# LTM8055_AddonBoard_v1_1.net
KiCad netlist of a schematic drawn in EAGLE
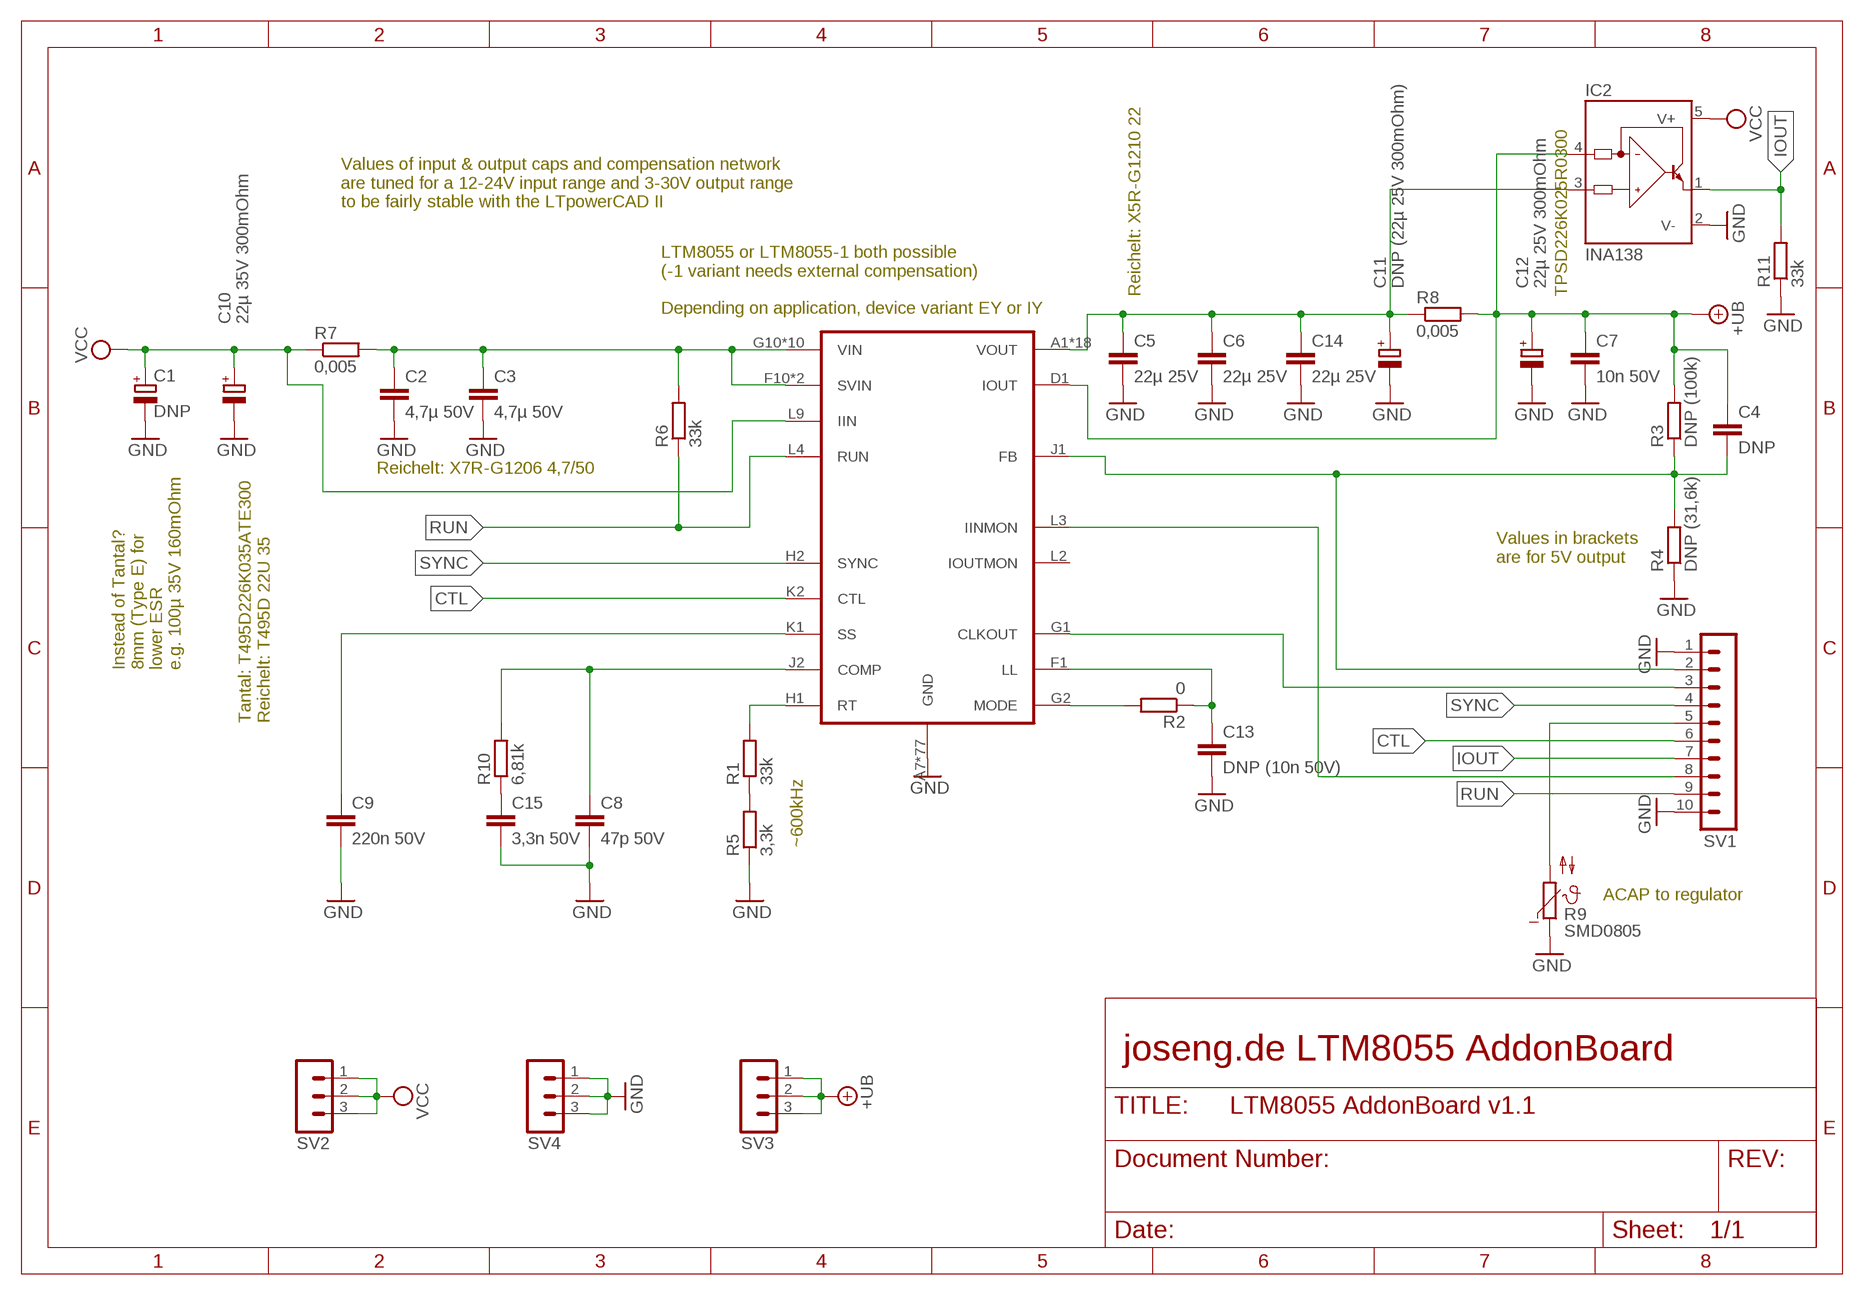
[diagram p0: schematic, sheet 1]

(export (version "E")
  (design (tool "Eeschema 10.0.6"))
  (components
    (comp (ref "C1")
      (value "DNP")
      (footprint "eagle-import:PANASONIC_E")
      (libsource (lib "eagle-import") (part "CPOL-EUE"))
    )
    (comp (ref "C2")
      (value "4,7µ 50V")
      (footprint "eagle-import:C1206")
      (libsource (lib "eagle-import") (part "C-EUC1206"))
    )
    (comp (ref "C3")
      (value "4,7µ 50V")
      (footprint "eagle-import:C1206")
      (libsource (lib "eagle-import") (part "C-EUC1206"))
    )
    (comp (ref "C4")
      (value "DNP")
      (footprint "eagle-import:C0805")
      (libsource (lib "eagle-import") (part "C-EUC0805"))
    )
    (comp (ref "C5")
      (value "22µ 25V")
      (footprint "eagle-import:C1210")
      (libsource (lib "eagle-import") (part "C-EUC1210"))
    )
    (comp (ref "C6")
      (value "22µ 25V")
      (footprint "eagle-import:C1210")
      (libsource (lib "eagle-import") (part "C-EUC1210"))
    )
    (comp (ref "C7")
      (value "10n 50V")
      (footprint "eagle-import:C0805")
      (libsource (lib "eagle-import") (part "C-EUC0805"))
    )
    (comp (ref "C8")
      (value "47p 50V")
      (footprint "eagle-import:C0805")
      (libsource (lib "eagle-import") (part "C-EUC0805"))
    )
    (comp (ref "C9")
      (value "220n 50V")
      (footprint "eagle-import:C0805")
      (libsource (lib "eagle-import") (part "C-EUC0805"))
    )
    (comp (ref "C10")
      (value "22µ 35V 300mOhm")
      (footprint "eagle-import:D_7343-31R")
      (libsource (lib "eagle-import") (part "CPOL-EUD/7343-31R"))
    )
    (comp (ref "C11")
      (value "DNP (22µ 25V 300mOhm)")
      (footprint "eagle-import:D_7343-31R")
      (libsource (lib "eagle-import") (part "CPOL-EUD/7343-31R"))
    )
    (comp (ref "C12")
      (value "22µ 25V 300mOhm")
      (footprint "eagle-import:D_7343-31R")
      (libsource (lib "eagle-import") (part "CPOL-EUD/7343-31R"))
    )
    (comp (ref "C13")
      (value "DNP (10n 50V)")
      (footprint "eagle-import:C0805")
      (libsource (lib "eagle-import") (part "C-EUC0805"))
    )
    (comp (ref "C14")
      (value "22µ 25V")
      (footprint "eagle-import:C1210")
      (libsource (lib "eagle-import") (part "C-EUC1210"))
    )
    (comp (ref "C15")
      (value "3,3n 50V")
      (footprint "eagle-import:C0805")
      (libsource (lib "eagle-import") (part "C-EUC0805"))
    )
    (comp (ref "IC1")
      (value "LTM8055-1")
      (footprint "eagle-import:BGA121_1.27_15X15MM")
      (libsource (lib "eagle-import") (part "LTM8055-1"))
    )
    (comp (ref "IC2")
      (value "INA138")
      (footprint "eagle-import:SOT23-5")
      (fields (field (name "MF") "TEXAS INSTRUMENTS") (field (name "MPN") "INA138NA/250"))
      (libsource (lib "eagle-import") (part "INA138"))
    )
    (comp (ref "R1")
      (value "33k")
      (footprint "eagle-import:R0805")
      (libsource (lib "eagle-import") (part "R-EU_R0805"))
    )
    (comp (ref "R2")
      (value "0")
      (footprint "eagle-import:R0805")
      (libsource (lib "eagle-import") (part "R-EU_R0805"))
    )
    (comp (ref "R3")
      (value "DNP (100k)")
      (footprint "eagle-import:R0805")
      (libsource (lib "eagle-import") (part "R-EU_R0805"))
    )
    (comp (ref "R4")
      (value "DNP (31,6k)")
      (footprint "eagle-import:R0805")
      (libsource (lib "eagle-import") (part "R-EU_R0805"))
    )
    (comp (ref "R5")
      (value "3,3k")
      (footprint "eagle-import:R0805")
      (libsource (lib "eagle-import") (part "R-EU_R0805"))
    )
    (comp (ref "R6")
      (value "33k")
      (footprint "eagle-import:R0805")
      (libsource (lib "eagle-import") (part "R-EU_R0805"))
    )
    (comp (ref "R7")
      (value "0,005")
      (footprint "eagle-import:R2512")
      (libsource (lib "eagle-import") (part "R-EU_R2512"))
    )
    (comp (ref "R8")
      (value "0,005")
      (footprint "eagle-import:R2512")
      (libsource (lib "eagle-import") (part "R-EU_R2512"))
    )
    (comp (ref "R9")
      (value "SMD0805")
      (footprint "eagle-import:R0805")
      (libsource (lib "eagle-import") (part "SMD0805"))
    )
    (comp (ref "R10")
      (value "6,81k")
      (footprint "eagle-import:R0805")
      (libsource (lib "eagle-import") (part "R-EU_R0805"))
    )
    (comp (ref "R11")
      (value "33k")
      (footprint "eagle-import:R0805")
      (libsource (lib "eagle-import") (part "R-EU_R0805"))
    )
    (comp (ref "SV1")
      (value "MA10-1")
      (footprint "eagle-import:MA10-1")
      (libsource (lib "eagle-import") (part "MA10-1"))
    )
    (comp (ref "SV2")
      (value "MA03-1")
      (footprint "eagle-import:MA03-1")
      (libsource (lib "eagle-import") (part "MA03-1"))
    )
    (comp (ref "SV3")
      (value "MA03-1")
      (footprint "eagle-import:MA03-1")
      (libsource (lib "eagle-import") (part "MA03-1"))
    )
    (comp (ref "SV4")
      (value "MA03-1")
      (footprint "eagle-import:MA03-1")
      (libsource (lib "eagle-import") (part "MA03-1"))
    )
  )
  (nets
    (net (code "1") (name "+UB") (class "Default")
      (node (ref "C12") (pin "+") (pinfunction "+_+") (pintype "passive"))
      (node (ref "C4") (pin "1") (pinfunction "1_1") (pintype "passive"))
      (node (ref "C7") (pin "1") (pinfunction "1_1") (pintype "passive"))
      (node (ref "IC1") (pin "D1") (pinfunction "IOUT_D1") (pintype "bidirectional"))
      (node (ref "IC2") (pin "4") (pinfunction "IN-_4") (pintype "input"))
      (node (ref "R3") (pin "2") (pinfunction "2_2") (pintype "passive"))
      (node (ref "R8") (pin "2") (pinfunction "2_2") (pintype "passive"))
      (node (ref "SV3") (pin "1") (pinfunction "1_1") (pintype "passive"))
      (node (ref "SV3") (pin "2") (pinfunction "2_2") (pintype "passive"))
      (node (ref "SV3") (pin "3") (pinfunction "3_3") (pintype "passive"))
    )
    (net (code "2") (name "CTL") (class "Default")
      (node (ref "IC1") (pin "K2") (pinfunction "CTL_K2") (pintype "bidirectional"))
      (node (ref "SV1") (pin "6") (pinfunction "6_6") (pintype "passive"))
    )
    (net (code "3") (name "GND") (class "Default")
      (node (ref "C1") (pin "-") (pinfunction "-_-") (pintype "passive"))
      (node (ref "C10") (pin "-") (pinfunction "-_-") (pintype "passive"))
      (node (ref "C11") (pin "-") (pinfunction "-_-") (pintype "passive"))
      (node (ref "C12") (pin "-") (pinfunction "-_-") (pintype "passive"))
      (node (ref "C13") (pin "2") (pinfunction "2_2") (pintype "passive"))
      (node (ref "C14") (pin "2") (pinfunction "2_2") (pintype "passive"))
      (node (ref "C15") (pin "2") (pinfunction "2_2") (pintype "passive"))
      (node (ref "C2") (pin "2") (pinfunction "2_2") (pintype "passive"))
      (node (ref "C3") (pin "2") (pinfunction "2_2") (pintype "passive"))
      (node (ref "C5") (pin "2") (pinfunction "2_2") (pintype "passive"))
      (node (ref "C6") (pin "2") (pinfunction "2_2") (pintype "passive"))
      (node (ref "C7") (pin "2") (pinfunction "2_2") (pintype "passive"))
      (node (ref "C8") (pin "2") (pinfunction "2_2") (pintype "passive"))
      (node (ref "C9") (pin "2") (pinfunction "2_2") (pintype "passive"))
      (node (ref "IC1") (pin "A10") (pinfunction "GND_A10") (pintype "bidirectional"))
      (node (ref "IC1") (pin "A11") (pinfunction "GND_A11") (pintype "bidirectional"))
      (node (ref "IC1") (pin "A7") (pinfunction "GND_A7") (pintype "bidirectional"))
      (node (ref "IC1") (pin "A8") (pinfunction "GND_A8") (pintype "bidirectional"))
      (node (ref "IC1") (pin "A9") (pinfunction "GND_A9") (pintype "bidirectional"))
      (node (ref "IC1") (pin "B10") (pinfunction "GND_B10") (pintype "bidirectional"))
      (node (ref "IC1") (pin "B11") (pinfunction "GND_B11") (pintype "bidirectional"))
      (node (ref "IC1") (pin "B7") (pinfunction "GND_B7") (pintype "bidirectional"))
      (node (ref "IC1") (pin "B8") (pinfunction "GND_B8") (pintype "bidirectional"))
      (node (ref "IC1") (pin "B9") (pinfunction "GND_B9") (pintype "bidirectional"))
      (node (ref "IC1") (pin "C10") (pinfunction "GND_C10") (pintype "bidirectional"))
      (node (ref "IC1") (pin "C11") (pinfunction "GND_C11") (pintype "bidirectional"))
      (node (ref "IC1") (pin "C7") (pinfunction "GND_C7") (pintype "bidirectional"))
      (node (ref "IC1") (pin "C8") (pinfunction "GND_C8") (pintype "bidirectional"))
      (node (ref "IC1") (pin "C9") (pinfunction "GND_C9") (pintype "bidirectional"))
      (node (ref "IC1") (pin "D10") (pinfunction "GND_D10") (pintype "bidirectional"))
      (node (ref "IC1") (pin "D11") (pinfunction "GND_D11") (pintype "bidirectional"))
      (node (ref "IC1") (pin "D2") (pinfunction "GND_D2") (pintype "bidirectional"))
      (node (ref "IC1") (pin "D3") (pinfunction "GND_D3") (pintype "bidirectional"))
      (node (ref "IC1") (pin "D4") (pinfunction "GND_D4") (pintype "bidirectional"))
      (node (ref "IC1") (pin "D5") (pinfunction "GND_D5") (pintype "bidirectional"))
      (node (ref "IC1") (pin "D6") (pinfunction "GND_D6") (pintype "bidirectional"))
      (node (ref "IC1") (pin "D7") (pinfunction "GND_D7") (pintype "bidirectional"))
      (node (ref "IC1") (pin "D8") (pinfunction "GND_D8") (pintype "bidirectional"))
      (node (ref "IC1") (pin "D9") (pinfunction "GND_D9") (pintype "bidirectional"))
      (node (ref "IC1") (pin "E1") (pinfunction "GND_E1") (pintype "bidirectional"))
      (node (ref "IC1") (pin "E10") (pinfunction "GND_E10") (pintype "bidirectional"))
      (node (ref "IC1") (pin "E11") (pinfunction "GND_E11") (pintype "bidirectional"))
      (node (ref "IC1") (pin "E2") (pinfunction "GND_E2") (pintype "bidirectional"))
      (node (ref "IC1") (pin "E3") (pinfunction "GND_E3") (pintype "bidirectional"))
      (node (ref "IC1") (pin "E4") (pinfunction "GND_E4") (pintype "bidirectional"))
      (node (ref "IC1") (pin "E5") (pinfunction "GND_E5") (pintype "bidirectional"))
      (node (ref "IC1") (pin "E6") (pinfunction "GND_E6") (pintype "bidirectional"))
      (node (ref "IC1") (pin "E7") (pinfunction "GND_E7") (pintype "bidirectional"))
      (node (ref "IC1") (pin "E8") (pinfunction "GND_E8") (pintype "bidirectional"))
      (node (ref "IC1") (pin "E9") (pinfunction "GND_E9") (pintype "bidirectional"))
      (node (ref "IC1") (pin "F2") (pinfunction "GND_F2") (pintype "bidirectional"))
      (node (ref "IC1") (pin "F3") (pinfunction "GND_F3") (pintype "bidirectional"))
      (node (ref "IC1") (pin "F4") (pinfunction "GND_F4") (pintype "bidirectional"))
      (node (ref "IC1") (pin "F5") (pinfunction "GND_F5") (pintype "bidirectional"))
      (node (ref "IC1") (pin "F6") (pinfunction "GND_F6") (pintype "bidirectional"))
      (node (ref "IC1") (pin "F7") (pinfunction "GND_F7") (pintype "bidirectional"))
      (node (ref "IC1") (pin "F8") (pinfunction "GND_F8") (pintype "bidirectional"))
      (node (ref "IC1") (pin "F9") (pinfunction "GND_F9") (pintype "bidirectional"))
      (node (ref "IC1") (pin "G3") (pinfunction "GND_G3") (pintype "bidirectional"))
      (node (ref "IC1") (pin "G4") (pinfunction "GND_G4") (pintype "bidirectional"))
      (node (ref "IC1") (pin "G5") (pinfunction "GND_G5") (pintype "bidirectional"))
      (node (ref "IC1") (pin "G6") (pinfunction "GND_G6") (pintype "bidirectional"))
      (node (ref "IC1") (pin "G7") (pinfunction "GND_G7") (pintype "bidirectional"))
      (node (ref "IC1") (pin "G8") (pinfunction "GND_G8") (pintype "bidirectional"))
      (node (ref "IC1") (pin "G9") (pinfunction "GND_G9") (pintype "bidirectional"))
      (node (ref "IC1") (pin "H3") (pinfunction "GND_H3") (pintype "bidirectional"))
      (node (ref "IC1") (pin "H4") (pinfunction "GND_H4") (pintype "bidirectional"))
      (node (ref "IC1") (pin "H5") (pinfunction "GND_H5") (pintype "bidirectional"))
      (node (ref "IC1") (pin "H6") (pinfunction "GND_H6") (pintype "bidirectional"))
      (node (ref "IC1") (pin "H7") (pinfunction "GND_H7") (pintype "bidirectional"))
      (node (ref "IC1") (pin "H8") (pinfunction "GND_H8") (pintype "bidirectional"))
      (node (ref "IC1") (pin "H9") (pinfunction "GND_H9") (pintype "bidirectional"))
      (node (ref "IC1") (pin "J3") (pinfunction "GND_J3") (pintype "bidirectional"))
      (node (ref "IC1") (pin "J4") (pinfunction "GND_J4") (pintype "bidirectional"))
      (node (ref "IC1") (pin "J5") (pinfunction "GND_J5") (pintype "bidirectional"))
      (node (ref "IC1") (pin "J6") (pinfunction "GND_J6") (pintype "bidirectional"))
      (node (ref "IC1") (pin "J7") (pinfunction "GND_J7") (pintype "bidirectional"))
      (node (ref "IC1") (pin "J8") (pinfunction "GND_J8") (pintype "bidirectional"))
      (node (ref "IC1") (pin "J9") (pinfunction "GND_J9") (pintype "bidirectional"))
      (node (ref "IC1") (pin "K3") (pinfunction "GND_K3") (pintype "bidirectional"))
      (node (ref "IC1") (pin "K4") (pinfunction "GND_K4") (pintype "bidirectional"))
      (node (ref "IC1") (pin "K5") (pinfunction "GND_K5") (pintype "bidirectional"))
      (node (ref "IC1") (pin "K6") (pinfunction "GND_K6") (pintype "bidirectional"))
      (node (ref "IC1") (pin "K7") (pinfunction "GND_K7") (pintype "bidirectional"))
      (node (ref "IC1") (pin "K8") (pinfunction "GND_K8") (pintype "bidirectional"))
      (node (ref "IC1") (pin "K9") (pinfunction "GND_K9") (pintype "bidirectional"))
      (node (ref "IC1") (pin "L1") (pinfunction "GND_L1") (pintype "bidirectional"))
      (node (ref "IC1") (pin "L5") (pinfunction "GND_L5") (pintype "bidirectional"))
      (node (ref "IC1") (pin "L6") (pinfunction "GND_L6") (pintype "bidirectional"))
      (node (ref "IC1") (pin "L7") (pinfunction "GND_L7") (pintype "bidirectional"))
      (node (ref "IC1") (pin "L8") (pinfunction "GND_L8") (pintype "bidirectional"))
      (node (ref "IC2") (pin "2") (pinfunction "V-_2") (pintype "power_in"))
      (node (ref "R11") (pin "1") (pinfunction "1_1") (pintype "passive"))
      (node (ref "R4") (pin "1") (pinfunction "1_1") (pintype "passive"))
      (node (ref "R5") (pin "1") (pinfunction "1_1") (pintype "passive"))
      (node (ref "R9") (pin "1") (pinfunction "1_1") (pintype "passive"))
      (node (ref "SV1") (pin "1") (pinfunction "1_1") (pintype "passive"))
      (node (ref "SV1") (pin "10") (pinfunction "10_10") (pintype "passive"))
      (node (ref "SV4") (pin "1") (pinfunction "1_1") (pintype "passive"))
      (node (ref "SV4") (pin "2") (pinfunction "2_2") (pintype "passive"))
      (node (ref "SV4") (pin "3") (pinfunction "3_3") (pintype "passive"))
    )
    (net (code "4") (name "IOUT") (class "Default")
      (node (ref "IC2") (pin "1") (pinfunction "OUT_1") (pintype "output"))
      (node (ref "R11") (pin "2") (pinfunction "2_2") (pintype "passive"))
      (node (ref "SV1") (pin "7") (pinfunction "7_7") (pintype "passive"))
    )
    (net (code "5") (name "Net-(C2-Pad1)") (class "Default")
      (node (ref "C2") (pin "1") (pinfunction "1_1") (pintype "passive"))
      (node (ref "C3") (pin "1") (pinfunction "1_1") (pintype "passive"))
      (node (ref "IC1") (pin "F10") (pinfunction "SVIN_F10") (pintype "bidirectional"))
      (node (ref "IC1") (pin "F11") (pinfunction "SVIN_F11") (pintype "bidirectional"))
      (node (ref "IC1") (pin "G10") (pinfunction "VIN_G10") (pintype "bidirectional"))
      (node (ref "IC1") (pin "G11") (pinfunction "VIN_G11") (pintype "bidirectional"))
      (node (ref "IC1") (pin "H10") (pinfunction "VIN_H10") (pintype "bidirectional"))
      (node (ref "IC1") (pin "H11") (pinfunction "VIN_H11") (pintype "bidirectional"))
      (node (ref "IC1") (pin "J10") (pinfunction "VIN_J10") (pintype "bidirectional"))
      (node (ref "IC1") (pin "J11") (pinfunction "VIN_J11") (pintype "bidirectional"))
      (node (ref "IC1") (pin "K10") (pinfunction "VIN_K10") (pintype "bidirectional"))
      (node (ref "IC1") (pin "K11") (pinfunction "VIN_K11") (pintype "bidirectional"))
      (node (ref "IC1") (pin "L10") (pinfunction "VIN_L10") (pintype "bidirectional"))
      (node (ref "IC1") (pin "L11") (pinfunction "VIN_L11") (pintype "bidirectional"))
      (node (ref "R6") (pin "2") (pinfunction "2_2") (pintype "passive"))
      (node (ref "R7") (pin "2") (pinfunction "2_2") (pintype "passive"))
    )
    (net (code "6") (name "Net-(C15-Pad1)") (class "Default")
      (node (ref "C15") (pin "1") (pinfunction "1_1") (pintype "passive"))
      (node (ref "R10") (pin "1") (pinfunction "1_1") (pintype "passive"))
    )
    (net (code "7") (name "Net-(IC1-CLKOUT)") (class "Default")
      (node (ref "IC1") (pin "G1") (pinfunction "CLKOUT_G1") (pintype "bidirectional"))
      (node (ref "SV1") (pin "3") (pinfunction "3_3") (pintype "passive"))
    )
    (net (code "8") (name "Net-(IC1-COMP)") (class "Default")
      (node (ref "C8") (pin "1") (pinfunction "1_1") (pintype "passive"))
      (node (ref "IC1") (pin "J2") (pinfunction "COMP_J2") (pintype "bidirectional"))
      (node (ref "R10") (pin "2") (pinfunction "2_2") (pintype "passive"))
    )
    (net (code "9") (name "Net-(IC1-FB)") (class "Default")
      (node (ref "C4") (pin "2") (pinfunction "2_2") (pintype "passive"))
      (node (ref "IC1") (pin "J1") (pinfunction "FB_J1") (pintype "bidirectional"))
      (node (ref "R3") (pin "1") (pinfunction "1_1") (pintype "passive"))
      (node (ref "R4") (pin "2") (pinfunction "2_2") (pintype "passive"))
      (node (ref "SV1") (pin "2") (pinfunction "2_2") (pintype "passive"))
    )
    (net (code "10") (name "Net-(IC1-IINMON)") (class "Default")
      (node (ref "IC1") (pin "L3") (pinfunction "IINMON_L3") (pintype "bidirectional"))
      (node (ref "SV1") (pin "8") (pinfunction "8_8") (pintype "passive"))
    )
    (net (code "11") (name "Net-(IC1-LL)") (class "Default")
      (node (ref "C13") (pin "1") (pinfunction "1_1") (pintype "passive"))
      (node (ref "IC1") (pin "F1") (pinfunction "LL_F1") (pintype "bidirectional"))
      (node (ref "R2") (pin "1") (pinfunction "1_1") (pintype "passive"))
    )
    (net (code "12") (name "Net-(IC1-MODE)") (class "Default")
      (node (ref "IC1") (pin "G2") (pinfunction "MODE_G2") (pintype "bidirectional"))
      (node (ref "R2") (pin "2") (pinfunction "2_2") (pintype "passive"))
    )
    (net (code "13") (name "Net-(IC1-RT)") (class "Default")
      (node (ref "IC1") (pin "H1") (pinfunction "RT_H1") (pintype "bidirectional"))
      (node (ref "R1") (pin "2") (pinfunction "2_2") (pintype "passive"))
    )
    (net (code "14") (name "Net-(IC1-SS)") (class "Default")
      (node (ref "C9") (pin "1") (pinfunction "1_1") (pintype "passive"))
      (node (ref "IC1") (pin "K1") (pinfunction "SS_K1") (pintype "bidirectional"))
    )
    (net (code "15") (name "Net-(IC2-IN+)") (class "Default")
      (node (ref "C11") (pin "+") (pinfunction "+_+") (pintype "passive"))
      (node (ref "C14") (pin "1") (pinfunction "1_1") (pintype "passive"))
      (node (ref "C5") (pin "1") (pinfunction "1_1") (pintype "passive"))
      (node (ref "C6") (pin "1") (pinfunction "1_1") (pintype "passive"))
      (node (ref "IC1") (pin "A1") (pinfunction "VOUT_A1") (pintype "bidirectional"))
      (node (ref "IC1") (pin "A2") (pinfunction "VOUT_A2") (pintype "bidirectional"))
      (node (ref "IC1") (pin "A3") (pinfunction "VOUT_A3") (pintype "bidirectional"))
      (node (ref "IC1") (pin "A4") (pinfunction "VOUT_A4") (pintype "bidirectional"))
      (node (ref "IC1") (pin "A5") (pinfunction "VOUT_A5") (pintype "bidirectional"))
      (node (ref "IC1") (pin "A6") (pinfunction "VOUT_A6") (pintype "bidirectional"))
      (node (ref "IC1") (pin "B1") (pinfunction "VOUT_B1") (pintype "bidirectional"))
      (node (ref "IC1") (pin "B2") (pinfunction "VOUT_B2") (pintype "bidirectional"))
      (node (ref "IC1") (pin "B3") (pinfunction "VOUT_B3") (pintype "bidirectional"))
      (node (ref "IC1") (pin "B4") (pinfunction "VOUT_B4") (pintype "bidirectional"))
      (node (ref "IC1") (pin "B5") (pinfunction "VOUT_B5") (pintype "bidirectional"))
      (node (ref "IC1") (pin "B6") (pinfunction "VOUT_B6") (pintype "bidirectional"))
      (node (ref "IC1") (pin "C1") (pinfunction "VOUT_C1") (pintype "bidirectional"))
      (node (ref "IC1") (pin "C2") (pinfunction "VOUT_C2") (pintype "bidirectional"))
      (node (ref "IC1") (pin "C3") (pinfunction "VOUT_C3") (pintype "bidirectional"))
      (node (ref "IC1") (pin "C4") (pinfunction "VOUT_C4") (pintype "bidirectional"))
      (node (ref "IC1") (pin "C5") (pinfunction "VOUT_C5") (pintype "bidirectional"))
      (node (ref "IC1") (pin "C6") (pinfunction "VOUT_C6") (pintype "bidirectional"))
      (node (ref "IC2") (pin "3") (pinfunction "IN+_3") (pintype "input"))
      (node (ref "R8") (pin "1") (pinfunction "1_1") (pintype "passive"))
    )
    (net (code "16") (name "Net-(R1-Pad1)") (class "Default")
      (node (ref "R1") (pin "1") (pinfunction "1_1") (pintype "passive"))
      (node (ref "R5") (pin "2") (pinfunction "2_2") (pintype "passive"))
    )
    (net (code "17") (name "Net-(R9-Pad2)") (class "Default")
      (node (ref "R9") (pin "2") (pinfunction "2_2") (pintype "passive"))
      (node (ref "SV1") (pin "5") (pinfunction "5_5") (pintype "passive"))
    )
    (net (code "18") (name "RUN") (class "Default")
      (node (ref "IC1") (pin "L4") (pinfunction "RUN_L4") (pintype "bidirectional"))
      (node (ref "R6") (pin "1") (pinfunction "1_1") (pintype "passive"))
      (node (ref "SV1") (pin "9") (pinfunction "9_9") (pintype "passive"))
    )
    (net (code "19") (name "SYNC") (class "Default")
      (node (ref "IC1") (pin "H2") (pinfunction "SYNC_H2") (pintype "bidirectional"))
      (node (ref "SV1") (pin "4") (pinfunction "4_4") (pintype "passive"))
    )
    (net (code "20") (name "VCC") (class "Default")
      (node (ref "C1") (pin "+") (pinfunction "+_+") (pintype "passive"))
      (node (ref "C10") (pin "+") (pinfunction "+_+") (pintype "passive"))
      (node (ref "IC1") (pin "L9") (pinfunction "IIN_L9") (pintype "bidirectional"))
      (node (ref "IC2") (pin "5") (pinfunction "V+_5") (pintype "power_in"))
      (node (ref "R7") (pin "1") (pinfunction "1_1") (pintype "passive"))
      (node (ref "SV2") (pin "1") (pinfunction "1_1") (pintype "passive"))
      (node (ref "SV2") (pin "2") (pinfunction "2_2") (pintype "passive"))
      (node (ref "SV2") (pin "3") (pinfunction "3_3") (pintype "passive"))
    )
    (net (code "21") (name "unconnected-(IC1-IOUTMON-PadL2)") (class "Default")
      (node (ref "IC1") (pin "L2") (pinfunction "IOUTMON_L2") (pintype "bidirectional"))
    )
  )
)
